# LiDAR_Demo_Board_Vert.net
KiCad netlist of a schematic drawn in EAGLE
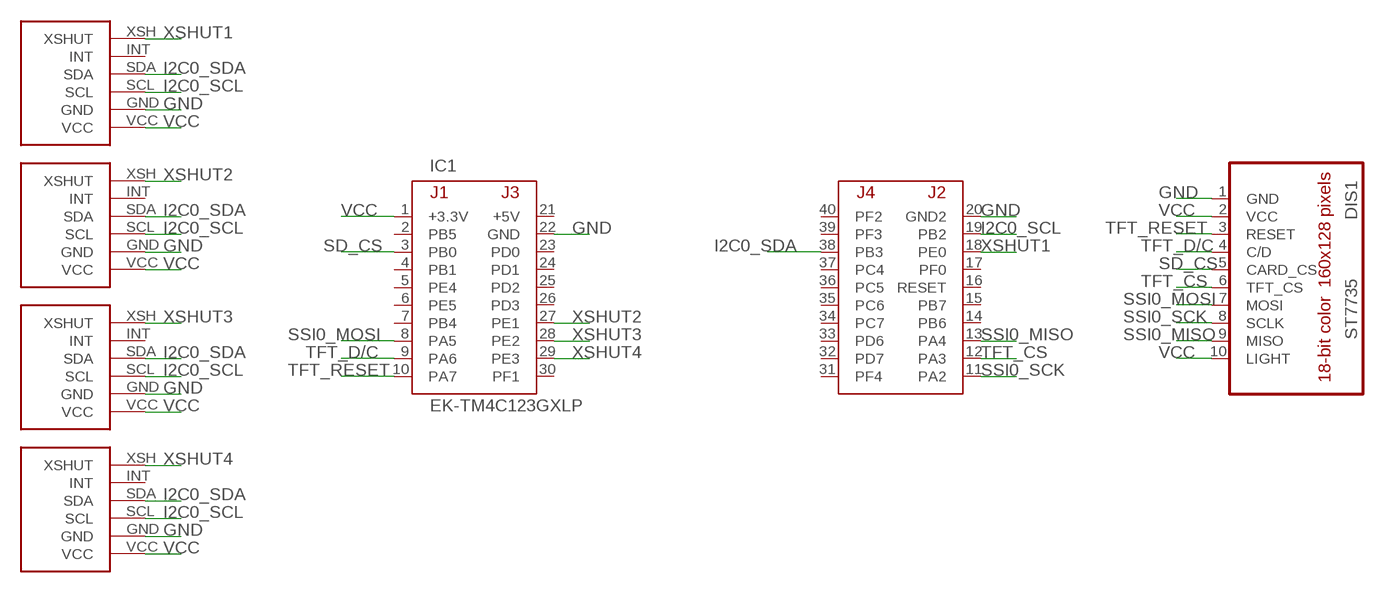
[diagram p0: schematic, sheet 1]

(export (version "E")
  (design (tool "Eeschema 10.0.6"))
  (components
    (comp (ref "DIS1")
      (value "ST7735")
      (footprint "eagle-import:ST7735")
      (libsource (lib "eagle-import") (part "ST7735"))
    )
    (comp (ref "IC1")
      (value "EK-TM4C123GXLP")
      (footprint "eagle-import:TM4C123LAUNCHPAD")
      (libsource (lib "eagle-import") (part "EK-TM4C123GXLP"))
    )
    (comp (ref "U$1")
      (value "LIDAR_VL53L0X_ATK_VERT")
      (footprint "eagle-import:LIDAR_VL53L0X_ATK_VERT")
      (libsource (lib "eagle-import") (part "LIDAR_VL53L0X_ATK_VERT"))
    )
    (comp (ref "U$2")
      (value "LIDAR_VL53L0X_ATK_VERT")
      (footprint "eagle-import:LIDAR_VL53L0X_ATK_VERT")
      (libsource (lib "eagle-import") (part "LIDAR_VL53L0X_ATK_VERT"))
    )
    (comp (ref "U$3")
      (value "LIDAR_VL53L0X_ATK_VERT")
      (footprint "eagle-import:LIDAR_VL53L0X_ATK_VERT")
      (libsource (lib "eagle-import") (part "LIDAR_VL53L0X_ATK_VERT"))
    )
    (comp (ref "U$4")
      (value "LIDAR_VL53L0X_ATK_VERT")
      (footprint "eagle-import:LIDAR_VL53L0X_ATK_VERT")
      (libsource (lib "eagle-import") (part "LIDAR_VL53L0X_ATK_VERT"))
    )
  )
  (nets
    (net (code "1") (name "/+5V") (class "Default")
      (node (ref "IC1") (pin "21") (pinfunction "+5V_21") (pintype "power_in"))
    )
    (net (code "2") (name "/GND") (class "Default")
      (node (ref "DIS1") (pin "1") (pinfunction "GND_1") (pintype "power_in"))
      (node (ref "IC1") (pin "20") (pinfunction "GND2_20") (pintype "power_in"))
      (node (ref "IC1") (pin "22") (pinfunction "GND_22") (pintype "power_in"))
      (node (ref "U$1") (pin "GND") (pinfunction "GND_GND") (pintype "bidirectional"))
      (node (ref "U$2") (pin "GND") (pinfunction "GND_GND") (pintype "bidirectional"))
      (node (ref "U$3") (pin "GND") (pinfunction "GND_GND") (pintype "bidirectional"))
      (node (ref "U$4") (pin "GND") (pinfunction "GND_GND") (pintype "bidirectional"))
    )
    (net (code "3") (name "/I2C0_SCL") (class "Default")
      (node (ref "IC1") (pin "19") (pinfunction "PB2_19") (pintype "bidirectional"))
      (node (ref "U$1") (pin "SCL") (pinfunction "SCL_SCL") (pintype "bidirectional"))
      (node (ref "U$2") (pin "SCL") (pinfunction "SCL_SCL") (pintype "bidirectional"))
      (node (ref "U$3") (pin "SCL") (pinfunction "SCL_SCL") (pintype "bidirectional"))
      (node (ref "U$4") (pin "SCL") (pinfunction "SCL_SCL") (pintype "bidirectional"))
    )
    (net (code "4") (name "/I2C0_SDA") (class "Default")
      (node (ref "IC1") (pin "38") (pinfunction "PB3_38") (pintype "bidirectional"))
      (node (ref "U$1") (pin "SDA") (pinfunction "SDA_SDA") (pintype "bidirectional"))
      (node (ref "U$2") (pin "SDA") (pinfunction "SDA_SDA") (pintype "bidirectional"))
      (node (ref "U$3") (pin "SDA") (pinfunction "SDA_SDA") (pintype "bidirectional"))
      (node (ref "U$4") (pin "SDA") (pinfunction "SDA_SDA") (pintype "bidirectional"))
    )
    (net (code "5") (name "/SD_CS") (class "Default")
      (node (ref "DIS1") (pin "5") (pinfunction "CARD_CS_5") (pintype "input"))
      (node (ref "IC1") (pin "3") (pinfunction "PB0_3") (pintype "bidirectional"))
    )
    (net (code "6") (name "/SSI0_MISO") (class "Default")
      (node (ref "DIS1") (pin "9") (pinfunction "MISO_9") (pintype "output"))
      (node (ref "IC1") (pin "13") (pinfunction "PA4_13") (pintype "bidirectional"))
    )
    (net (code "7") (name "/SSI0_MOSI") (class "Default")
      (node (ref "DIS1") (pin "7") (pinfunction "MOSI_7") (pintype "input"))
      (node (ref "IC1") (pin "8") (pinfunction "PA5_8") (pintype "bidirectional"))
    )
    (net (code "8") (name "/SSI0_SCK") (class "Default")
      (node (ref "DIS1") (pin "8") (pinfunction "SCLK_8") (pintype "input"))
      (node (ref "IC1") (pin "11") (pinfunction "PA2_11") (pintype "bidirectional"))
    )
    (net (code "9") (name "/TFT_CS") (class "Default")
      (node (ref "DIS1") (pin "6") (pinfunction "TFT_CS_6") (pintype "input"))
      (node (ref "IC1") (pin "12") (pinfunction "PA3_12") (pintype "bidirectional"))
    )
    (net (code "10") (name "/TFT_D{slash}C") (class "Default")
      (node (ref "DIS1") (pin "4") (pinfunction "C/D_4") (pintype "input"))
      (node (ref "IC1") (pin "9") (pinfunction "PA6_9") (pintype "bidirectional"))
    )
    (net (code "11") (name "/TFT_RESET") (class "Default")
      (node (ref "DIS1") (pin "3") (pinfunction "RESET_3") (pintype "input"))
      (node (ref "IC1") (pin "10") (pinfunction "PA7_10") (pintype "bidirectional"))
    )
    (net (code "12") (name "/VCC") (class "Default")
      (node (ref "DIS1") (pin "10") (pinfunction "LIGHT_10") (pintype "passive"))
      (node (ref "DIS1") (pin "2") (pinfunction "VCC_2") (pintype "power_in"))
      (node (ref "IC1") (pin "1") (pinfunction "+3.3V_1") (pintype "power_in"))
      (node (ref "U$1") (pin "VCC") (pinfunction "VCC_VCC") (pintype "bidirectional"))
      (node (ref "U$2") (pin "VCC") (pinfunction "VCC_VCC") (pintype "bidirectional"))
      (node (ref "U$3") (pin "VCC") (pinfunction "VCC_VCC") (pintype "bidirectional"))
      (node (ref "U$4") (pin "VCC") (pinfunction "VCC_VCC") (pintype "bidirectional"))
    )
    (net (code "13") (name "/XSHUT1") (class "Default")
      (node (ref "IC1") (pin "18") (pinfunction "PE0_18") (pintype "bidirectional"))
      (node (ref "U$1") (pin "XSH") (pinfunction "XSHUT_XSH") (pintype "bidirectional"))
    )
    (net (code "14") (name "/XSHUT2") (class "Default")
      (node (ref "IC1") (pin "27") (pinfunction "PE1_27") (pintype "bidirectional"))
      (node (ref "U$2") (pin "XSH") (pinfunction "XSHUT_XSH") (pintype "bidirectional"))
    )
    (net (code "15") (name "/XSHUT3") (class "Default")
      (node (ref "IC1") (pin "28") (pinfunction "PE2_28") (pintype "bidirectional"))
      (node (ref "U$3") (pin "XSH") (pinfunction "XSHUT_XSH") (pintype "bidirectional"))
    )
    (net (code "16") (name "/XSHUT4") (class "Default")
      (node (ref "IC1") (pin "29") (pinfunction "PE3_29") (pintype "bidirectional"))
      (node (ref "U$4") (pin "XSH") (pinfunction "XSHUT_XSH") (pintype "bidirectional"))
    )
    (net (code "17") (name "unconnected-(IC1-PB1-Pad4)") (class "Default")
      (node (ref "IC1") (pin "4") (pinfunction "PB1_4") (pintype "bidirectional"))
    )
    (net (code "18") (name "unconnected-(IC1-PB4-Pad7)") (class "Default")
      (node (ref "IC1") (pin "7") (pinfunction "PB4_7") (pintype "bidirectional"))
    )
    (net (code "19") (name "unconnected-(IC1-PB5-Pad2)") (class "Default")
      (node (ref "IC1") (pin "2") (pinfunction "PB5_2") (pintype "bidirectional"))
    )
    (net (code "20") (name "unconnected-(IC1-PB6-Pad14)") (class "Default")
      (node (ref "IC1") (pin "14") (pinfunction "PB6_14") (pintype "bidirectional"))
    )
    (net (code "21") (name "unconnected-(IC1-PB7-Pad15)") (class "Default")
      (node (ref "IC1") (pin "15") (pinfunction "PB7_15") (pintype "bidirectional"))
    )
    (net (code "22") (name "unconnected-(IC1-PC4-Pad37)") (class "Default")
      (node (ref "IC1") (pin "37") (pinfunction "PC4_37") (pintype "bidirectional"))
    )
    (net (code "23") (name "unconnected-(IC1-PC5-Pad36)") (class "Default")
      (node (ref "IC1") (pin "36") (pinfunction "PC5_36") (pintype "bidirectional"))
    )
    (net (code "24") (name "unconnected-(IC1-PC6-Pad35)") (class "Default")
      (node (ref "IC1") (pin "35") (pinfunction "PC6_35") (pintype "bidirectional"))
    )
    (net (code "25") (name "unconnected-(IC1-PC7-Pad34)") (class "Default")
      (node (ref "IC1") (pin "34") (pinfunction "PC7_34") (pintype "bidirectional"))
    )
    (net (code "26") (name "unconnected-(IC1-PD0-Pad23)") (class "Default")
      (node (ref "IC1") (pin "23") (pinfunction "PD0_23") (pintype "bidirectional"))
    )
    (net (code "27") (name "unconnected-(IC1-PD1-Pad24)") (class "Default")
      (node (ref "IC1") (pin "24") (pinfunction "PD1_24") (pintype "bidirectional"))
    )
    (net (code "28") (name "unconnected-(IC1-PD2-Pad25)") (class "Default")
      (node (ref "IC1") (pin "25") (pinfunction "PD2_25") (pintype "bidirectional"))
    )
    (net (code "29") (name "unconnected-(IC1-PD3-Pad26)") (class "Default")
      (node (ref "IC1") (pin "26") (pinfunction "PD3_26") (pintype "bidirectional"))
    )
    (net (code "30") (name "unconnected-(IC1-PD6-Pad33)") (class "Default")
      (node (ref "IC1") (pin "33") (pinfunction "PD6_33") (pintype "bidirectional"))
    )
    (net (code "31") (name "unconnected-(IC1-PD7-Pad32)") (class "Default")
      (node (ref "IC1") (pin "32") (pinfunction "PD7_32") (pintype "bidirectional"))
    )
    (net (code "32") (name "unconnected-(IC1-PE4-Pad5)") (class "Default")
      (node (ref "IC1") (pin "5") (pinfunction "PE4_5") (pintype "bidirectional"))
    )
    (net (code "33") (name "unconnected-(IC1-PE5-Pad6)") (class "Default")
      (node (ref "IC1") (pin "6") (pinfunction "PE5_6") (pintype "bidirectional"))
    )
    (net (code "34") (name "unconnected-(IC1-PF0-Pad17)") (class "Default")
      (node (ref "IC1") (pin "17") (pinfunction "PF0_17") (pintype "bidirectional"))
    )
    (net (code "35") (name "unconnected-(IC1-PF1-Pad30)") (class "Default")
      (node (ref "IC1") (pin "30") (pinfunction "PF1_30") (pintype "bidirectional"))
    )
    (net (code "36") (name "unconnected-(IC1-PF2-Pad40)") (class "Default")
      (node (ref "IC1") (pin "40") (pinfunction "PF2_40") (pintype "bidirectional"))
    )
    (net (code "37") (name "unconnected-(IC1-PF3-Pad39)") (class "Default")
      (node (ref "IC1") (pin "39") (pinfunction "PF3_39") (pintype "bidirectional"))
    )
    (net (code "38") (name "unconnected-(IC1-PF4-Pad31)") (class "Default")
      (node (ref "IC1") (pin "31") (pinfunction "PF4_31") (pintype "bidirectional"))
    )
    (net (code "39") (name "unconnected-(IC1-RESET-Pad16)") (class "Default")
      (node (ref "IC1") (pin "16") (pinfunction "RESET_16") (pintype "input"))
    )
    (net (code "40") (name "unconnected-(U$1-PadINT)") (class "Default")
      (node (ref "U$1") (pin "INT") (pinfunction "INT_INT") (pintype "bidirectional"))
    )
    (net (code "41") (name "unconnected-(U$2-PadINT)") (class "Default")
      (node (ref "U$2") (pin "INT") (pinfunction "INT_INT") (pintype "bidirectional"))
    )
    (net (code "42") (name "unconnected-(U$3-PadINT)") (class "Default")
      (node (ref "U$3") (pin "INT") (pinfunction "INT_INT") (pintype "bidirectional"))
    )
    (net (code "43") (name "unconnected-(U$4-PadINT)") (class "Default")
      (node (ref "U$4") (pin "INT") (pinfunction "INT_INT") (pintype "bidirectional"))
    )
  )
)
